# Debugger.net
KiCad netlist of a schematic drawn in Altium Designer
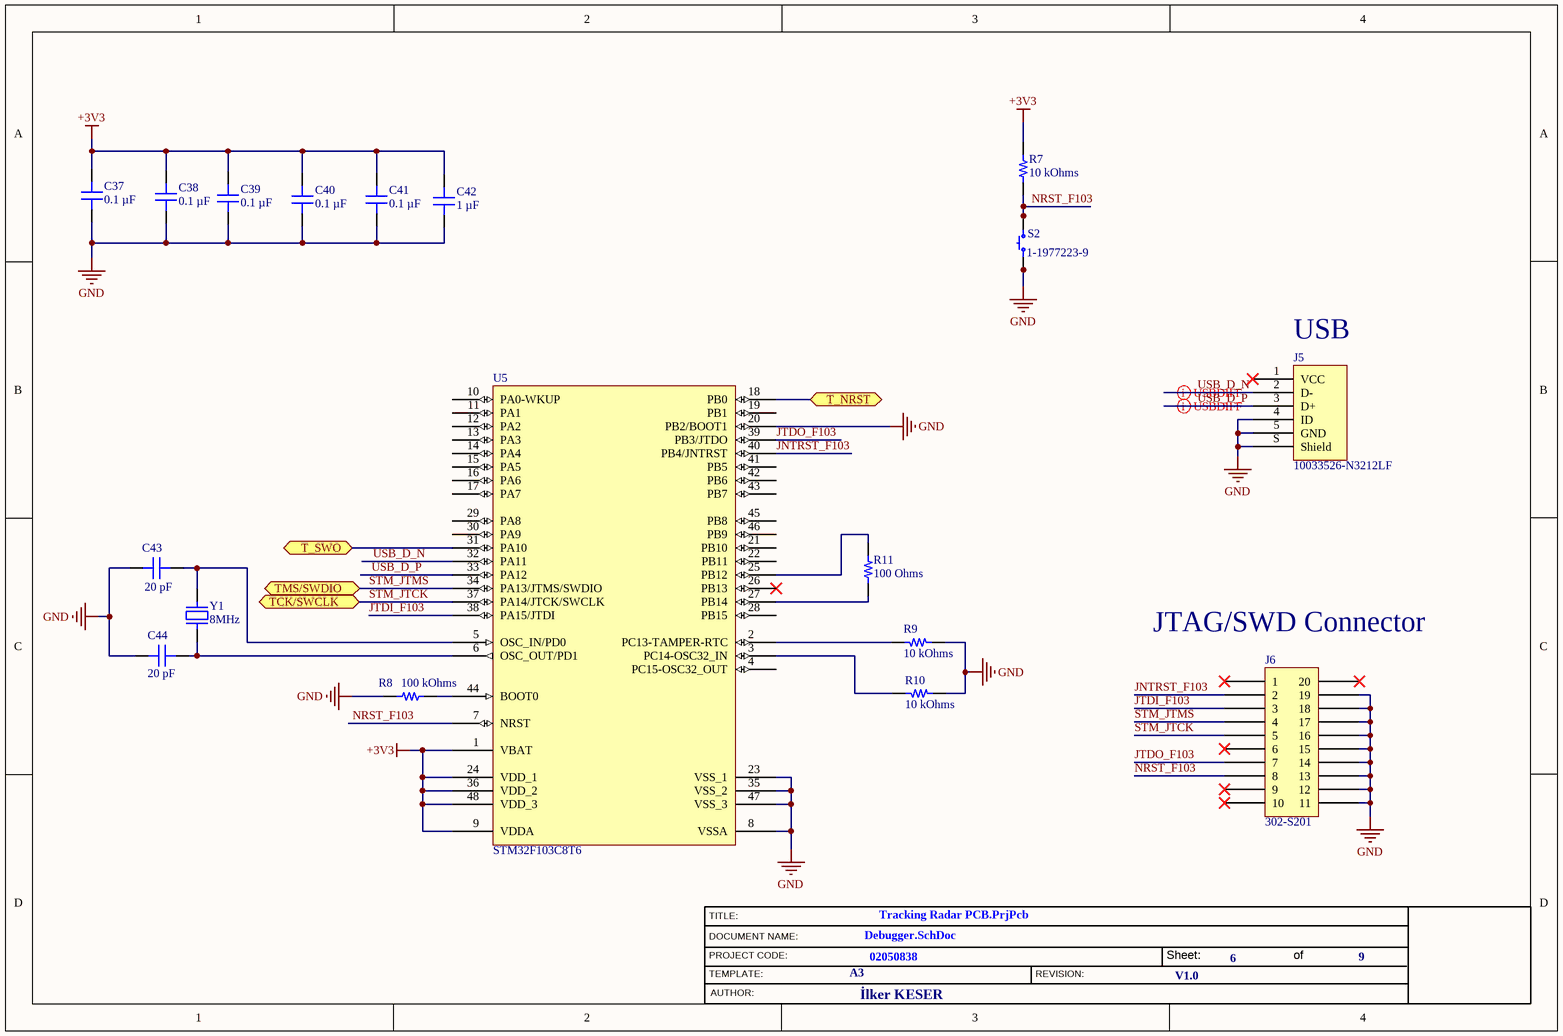
[diagram p0: Debugger.SchDoc]

(export (version "E")
  (design (tool "Eeschema 10.0.6"))
  (components
    (comp (ref "C37")
      (value "0.1 µF")
      (footprint "CAP 0402_1005")
      (description "CAP CER 0.1UF 6.3V X5R 0402")
      (fields
        (field (name "PART NUMBER") "C0402C104M9PAC7867")
        (field (name "CAPACITANCE") "0.1 µF")
        (field (name "MANUFACTURER") "KEMET")
      )
      (libsource (lib "Celestial Altium Library - altium_library") (part "Capacitor"))
    )
    (comp (ref "C38")
      (value "0.1 µF")
      (footprint "CAP 0402_1005")
      (description "CAP CER 0.1UF 6.3V X5R 0402")
      (fields
        (field (name "PART NUMBER") "C0402C104M9PAC7867")
        (field (name "CAPACITANCE") "0.1 µF")
        (field (name "MANUFACTURER") "KEMET")
      )
      (libsource (lib "Celestial Altium Library - altium_library") (part "Capacitor"))
    )
    (comp (ref "C39")
      (value "0.1 µF")
      (footprint "CAP 0402_1005")
      (description "CAP CER 0.1UF 6.3V X5R 0402")
      (fields
        (field (name "PART NUMBER") "C0402C104M9PAC7867")
        (field (name "CAPACITANCE") "0.1 µF")
        (field (name "MANUFACTURER") "KEMET")
      )
      (libsource (lib "Celestial Altium Library - altium_library") (part "Capacitor"))
    )
    (comp (ref "C40")
      (value "0.1 µF")
      (footprint "CAP 0402_1005")
      (description "CAP CER 0.1UF 6.3V X5R 0402")
      (fields
        (field (name "PART NUMBER") "C0402C104M9PAC7867")
        (field (name "CAPACITANCE") "0.1 µF")
        (field (name "MANUFACTURER") "KEMET")
      )
      (libsource (lib "Celestial Altium Library - altium_library") (part "Capacitor"))
    )
    (comp (ref "C41")
      (value "0.1 µF")
      (footprint "CAP 0402_1005")
      (description "CAP CER 0.1UF 6.3V X5R 0402")
      (fields
        (field (name "PART NUMBER") "C0402C104M9PAC7867")
        (field (name "CAPACITANCE") "0.1 µF")
        (field (name "MANUFACTURER") "KEMET")
      )
      (libsource (lib "Celestial Altium Library - altium_library") (part "Capacitor"))
    )
    (comp (ref "C42")
      (value "1 µF")
      (footprint "CAP 0402_1005")
      (description "CAP CER 1UF 6.3V X5R 0402")
      (fields
        (field (name "PART NUMBER") "GRM152R60J105ME15D")
        (field (name "CAPACITANCE") "1 µF")
        (field (name "MANUFACTURER") "Murata Electronics")
      )
      (libsource (lib "Celestial Altium Library - altium_library") (part "Capacitor"))
    )
    (comp (ref "C43")
      (value "20 pF")
      (footprint "CAP 0402_1005")
      (description "CAP CER 20PF 10V NP0 0402")
      (fields
        (field (name "PART NUMBER") "C0402C200K8GAC7867")
        (field (name "CAPACITANCE") "20 pF")
        (field (name "MANUFACTURER") "KEMET")
      )
      (libsource (lib "Celestial Altium Library - altium_library") (part "Capacitor"))
    )
    (comp (ref "C44")
      (value "20 pF")
      (footprint "CAP 0402_1005")
      (description "CAP CER 20PF 10V NP0 0402")
      (fields
        (field (name "PART NUMBER") "C0402C200K8GAC7867")
        (field (name "CAPACITANCE") "20 pF")
        (field (name "MANUFACTURER") "KEMET")
      )
      (libsource (lib "Celestial Altium Library - altium_library") (part "Capacitor"))
    )
    (comp (ref "J5")
      (value "10033526-N3212LF")
      (footprint "FCI USB 10033526-N3212LF")
      (description "CONN RCPT MINI USB B 5POS SMD RA")
      (fields (field (name "MANUFACTURER") "Amphenol ICC (FCI)"))
      (libsource (lib "Celestial Altium Library - altium_library") (part "USB 2.0 Type B Micro"))
    )
    (comp (ref "J6")
      (value "302-S201")
      (footprint "OST 302-S201")
      (description "CONN HEADER VERT 20POS 2.54MM")
      (fields (field (name "MANUFACTURER") "On Shore Technology Inc."))
      (libsource (lib "Celestial Altium Library - altium_library") (part "20 Pin Dual Row"))
    )
    (comp (ref "R7")
      (value "10 kOhms")
      (footprint "KOA RES RK73 RN73 0402_1005")
      (description "RES 10K OHM 0.5% 1/10W 0402")
      (fields
        (field (name "PART NUMBER") "RK73H1ETTP1002D")
        (field (name "MANUFACTURER") "KOA Speer Electronics, Inc.")
      )
      (libsource (lib "Celestial Altium Library - altium_library") (part "Resistor"))
    )
    (comp (ref "R8")
      (value "100 kOhms")
      (footprint "YAGEO RES 0402_1005")
      (description "RES 100K OHM 0.1% 1/16W 0402")
      (fields (field (name "PART NUMBER") "RP0402BRD07100KL") (field (name "MANUFACTURER") "Yageo"))
      (libsource (lib "Celestial Altium Library - altium_library") (part "Resistor"))
    )
    (comp (ref "R9")
      (value "10 kOhms")
      (footprint "KOA RES RK73 RN73 0402_1005")
      (description "RES 10K OHM 0.5% 1/10W 0402")
      (fields
        (field (name "PART NUMBER") "RK73H1ETTP1002D")
        (field (name "MANUFACTURER") "KOA Speer Electronics, Inc.")
      )
      (libsource (lib "Celestial Altium Library - altium_library") (part "Resistor"))
    )
    (comp (ref "R10")
      (value "10 kOhms")
      (footprint "KOA RES RK73 RN73 0402_1005")
      (description "RES 10K OHM 0.5% 1/10W 0402")
      (fields
        (field (name "PART NUMBER") "RK73H1ETTP1002D")
        (field (name "MANUFACTURER") "KOA Speer Electronics, Inc.")
      )
      (libsource (lib "Celestial Altium Library - altium_library") (part "Resistor"))
    )
    (comp (ref "R11")
      (value "100 Ohms")
      (footprint "YAGEO RES 0402_1005")
      (description "RES 100 OHM 0.1% 1/16W 0402")
      (fields (field (name "PART NUMBER") "RP0402BRD07100RL") (field (name "MANUFACTURER") "Yageo"))
      (libsource (lib "Celestial Altium Library - altium_library") (part "Resistor"))
    )
    (comp (ref "S2")
      (value "1-1977223-9")
      (footprint "TE FSM6JSMA")
      (description "SWITCH TACTILE SPST-NO 0.05A 24V")
      (fields (field (name "MANUFACTURER") "TE Connectivity ALCOSWITCH Switches"))
      (libsource (lib "Celestial Altium Library - altium_library") (part "SPST-NO 4 PIN"))
    )
    (comp (ref "U5")
      (value "STM32F103C8T6")
      (footprint "LQFP48_L")
      (description "STM32 ARM-based 32-bit MCU with 64 Kbytes Flash, 48-pin LQFP, Industrial Temperature")
      (fields (field (name "PUBLISHER") "Altium Limited"))
      (libsource (lib "ST Microcontroller 32-Bit STM32") (part "STM32F103C8T6"))
    )
    (comp (ref "Y1")
      (value "8MHz")
      (footprint "TXC 9C")
      (description "CRYSTAL 8.0000MHZ 20PF SMD")
      (fields (field (name "PART NUMBER") "9C-8.000MBBK-T") (field (name "MANUFACTURER") "TXC CORPORATION"))
      (libsource (lib "Celestial Altium Library - altium_library") (part "TXC Crystal 9C"))
    )
  )
  (nets
    (net (code "1") (name "+3V3") (class "Default")
      (node (ref "C37") (pin "2") (pinfunction "2_2") (pintype "passive"))
      (node (ref "C38") (pin "2") (pinfunction "2_2") (pintype "passive"))
      (node (ref "C39") (pin "2") (pinfunction "2_2") (pintype "passive"))
      (node (ref "C40") (pin "2") (pinfunction "2_2") (pintype "passive"))
      (node (ref "C41") (pin "2") (pinfunction "2_2") (pintype "passive"))
      (node (ref "C42") (pin "2") (pinfunction "2_2") (pintype "passive"))
      (node (ref "R7") (pin "1") (pinfunction "1_1") (pintype "passive"))
      (node (ref "U5") (pin "1") (pinfunction "VBAT_1") (pintype "power_in"))
      (node (ref "U5") (pin "24") (pinfunction "VDD_1_24") (pintype "power_in"))
      (node (ref "U5") (pin "36") (pinfunction "VDD_2_36") (pintype "power_in"))
      (node (ref "U5") (pin "48") (pinfunction "VDD_3_48") (pintype "power_in"))
      (node (ref "U5") (pin "9") (pinfunction "VDDA_9") (pintype "power_in"))
    )
    (net (code "2") (name "/JNTRST_F103") (class "Default")
      (node (ref "J6") (pin "2") (pinfunction "2_2") (pintype "passive"))
      (node (ref "U5") (pin "40") (pinfunction "PB4/JNTRST_40") (pintype "bidirectional"))
    )
    (net (code "3") (name "/JTDI_F103") (class "Default")
      (node (ref "J6") (pin "3") (pinfunction "3_3") (pintype "passive"))
      (node (ref "U5") (pin "38") (pinfunction "PA15/JTDI_38") (pintype "bidirectional"))
    )
    (net (code "4") (name "/JTDO_F103") (class "Default")
      (node (ref "J6") (pin "7") (pinfunction "7_7") (pintype "passive"))
      (node (ref "U5") (pin "39") (pinfunction "PB3/JTDO_39") (pintype "bidirectional"))
    )
    (net (code "5") (name "/NRST_F103") (class "Default")
      (node (ref "J6") (pin "8") (pinfunction "8_8") (pintype "passive"))
      (node (ref "R7") (pin "2") (pinfunction "2_2") (pintype "passive"))
      (node (ref "S2") (pin "3") (pinfunction "3_3") (pintype "passive"))
      (node (ref "S2") (pin "4") (pinfunction "4_4") (pintype "passive"))
      (node (ref "U5") (pin "7") (pinfunction "NRST_7") (pintype "bidirectional"))
    )
    (net (code "6") (name "/STM_JTCK") (class "Default")
      (node (ref "J6") (pin "5") (pinfunction "5_5") (pintype "passive"))
      (node (ref "U5") (pin "37") (pinfunction "PA14/JTCK/SWCLK_37") (pintype "bidirectional"))
    )
    (net (code "7") (name "/STM_JTMS") (class "Default")
      (node (ref "J6") (pin "4") (pinfunction "4_4") (pintype "passive"))
      (node (ref "U5") (pin "34") (pinfunction "PA13/JTMS/SWDIO_34") (pintype "bidirectional"))
    )
    (net (code "8") (name "/T_NRST") (class "Default")
      (node (ref "U5") (pin "18") (pinfunction "PB0_18") (pintype "bidirectional"))
    )
    (net (code "9") (name "/T_SWO") (class "Default")
      (node (ref "U5") (pin "31") (pinfunction "PA10_31") (pintype "bidirectional"))
    )
    (net (code "10") (name "/USB_D_N") (class "Default")
      (node (ref "J5") (pin "2") (pinfunction "D-_2") (pintype "passive"))
      (node (ref "U5") (pin "32") (pinfunction "PA11_32") (pintype "bidirectional"))
    )
    (net (code "11") (name "/USB_D_P") (class "Default")
      (node (ref "J5") (pin "3") (pinfunction "D+_3") (pintype "passive"))
      (node (ref "U5") (pin "33") (pinfunction "PA12_33") (pintype "bidirectional"))
    )
    (net (code "12") (name "GND") (class "Default")
      (node (ref "C37") (pin "1") (pinfunction "1_1") (pintype "passive"))
      (node (ref "C38") (pin "1") (pinfunction "1_1") (pintype "passive"))
      (node (ref "C39") (pin "1") (pinfunction "1_1") (pintype "passive"))
      (node (ref "C40") (pin "1") (pinfunction "1_1") (pintype "passive"))
      (node (ref "C41") (pin "1") (pinfunction "1_1") (pintype "passive"))
      (node (ref "C42") (pin "1") (pinfunction "1_1") (pintype "passive"))
      (node (ref "C43") (pin "1") (pinfunction "1_1") (pintype "passive"))
      (node (ref "C44") (pin "1") (pinfunction "1_1") (pintype "passive"))
      (node (ref "J5") (pin "4") (pinfunction "ID_4") (pintype "passive"))
      (node (ref "J5") (pin "5") (pinfunction "GND_5") (pintype "passive"))
      (node (ref "J5") (pin "S") (pinfunction "Shield_S") (pintype "passive"))
      (node (ref "J6") (pin "11") (pinfunction "11_11") (pintype "passive"))
      (node (ref "J6") (pin "12") (pinfunction "12_12") (pintype "passive"))
      (node (ref "J6") (pin "13") (pinfunction "13_13") (pintype "passive"))
      (node (ref "J6") (pin "14") (pinfunction "14_14") (pintype "passive"))
      (node (ref "J6") (pin "15") (pinfunction "15_15") (pintype "passive"))
      (node (ref "J6") (pin "16") (pinfunction "16_16") (pintype "passive"))
      (node (ref "J6") (pin "17") (pinfunction "17_17") (pintype "passive"))
      (node (ref "J6") (pin "18") (pinfunction "18_18") (pintype "passive"))
      (node (ref "J6") (pin "19") (pinfunction "19_19") (pintype "passive"))
      (node (ref "R10") (pin "2") (pinfunction "2_2") (pintype "passive"))
      (node (ref "R8") (pin "1") (pinfunction "1_1") (pintype "passive"))
      (node (ref "R9") (pin "2") (pinfunction "2_2") (pintype "passive"))
      (node (ref "S2") (pin "1") (pinfunction "1_1") (pintype "passive"))
      (node (ref "S2") (pin "2") (pinfunction "2_2") (pintype "passive"))
      (node (ref "U5") (pin "20") (pinfunction "PB2/BOOT1_20") (pintype "bidirectional"))
      (node (ref "U5") (pin "23") (pinfunction "VSS_1_23") (pintype "power_in"))
      (node (ref "U5") (pin "35") (pinfunction "VSS_2_35") (pintype "power_in"))
      (node (ref "U5") (pin "47") (pinfunction "VSS_3_47") (pintype "power_in"))
      (node (ref "U5") (pin "8") (pinfunction "VSSA_8") (pintype "power_in"))
    )
    (net (code "13") (name "Net-(U5-BOOT0)") (class "Default")
      (node (ref "R8") (pin "2") (pinfunction "2_2") (pintype "passive"))
      (node (ref "U5") (pin "44") (pinfunction "BOOT0_44") (pintype "input"))
    )
    (net (code "14") (name "Net-(U5-OSC_IN{slash}PD0)") (class "Default")
      (node (ref "C43") (pin "2") (pinfunction "2_2") (pintype "passive"))
      (node (ref "U5") (pin "5") (pinfunction "OSC_IN/PD0_5") (pintype "input"))
      (node (ref "Y1") (pin "2") (pinfunction "2_2") (pintype "passive"))
    )
    (net (code "15") (name "Net-(U5-OSC_OUT{slash}PD1)") (class "Default")
      (node (ref "C44") (pin "2") (pinfunction "2_2") (pintype "passive"))
      (node (ref "U5") (pin "6") (pinfunction "OSC_OUT/PD1_6") (pintype "output"))
      (node (ref "Y1") (pin "1") (pinfunction "1_1") (pintype "passive"))
    )
    (net (code "16") (name "Net-(U5-PB12)") (class "Default")
      (node (ref "R11") (pin "2") (pinfunction "2_2") (pintype "passive"))
      (node (ref "U5") (pin "25") (pinfunction "PB12_25") (pintype "bidirectional"))
    )
    (net (code "17") (name "Net-(U5-PB14)") (class "Default")
      (node (ref "R11") (pin "1") (pinfunction "1_1") (pintype "passive"))
      (node (ref "U5") (pin "27") (pinfunction "PB14_27") (pintype "bidirectional"))
    )
    (net (code "18") (name "Net-(U5-PC13-TAMPER-RTC)") (class "Default")
      (node (ref "R9") (pin "1") (pinfunction "1_1") (pintype "passive"))
      (node (ref "U5") (pin "2") (pinfunction "PC13-TAMPER-RTC_2") (pintype "bidirectional"))
    )
    (net (code "19") (name "Net-(U5-PC14-OSC32_IN)") (class "Default")
      (node (ref "R10") (pin "1") (pinfunction "1_1") (pintype "passive"))
      (node (ref "U5") (pin "3") (pinfunction "PC14-OSC32_IN_3") (pintype "bidirectional"))
    )
    (net (code "20") (name "unconnected-(J5-VCC-Pad1)") (class "Default")
      (node (ref "J5") (pin "1") (pinfunction "VCC_1") (pintype "passive+no_connect"))
    )
    (net (code "21") (name "unconnected-(J6-Pad1)") (class "Default")
      (node (ref "J6") (pin "1") (pinfunction "1_1") (pintype "passive+no_connect"))
    )
    (net (code "22") (name "unconnected-(J6-Pad6)") (class "Default")
      (node (ref "J6") (pin "6") (pinfunction "6_6") (pintype "passive+no_connect"))
    )
    (net (code "23") (name "unconnected-(J6-Pad9)") (class "Default")
      (node (ref "J6") (pin "9") (pinfunction "9_9") (pintype "passive+no_connect"))
    )
    (net (code "24") (name "unconnected-(J6-Pad10)") (class "Default")
      (node (ref "J6") (pin "10") (pinfunction "10_10") (pintype "passive+no_connect"))
    )
    (net (code "25") (name "unconnected-(J6-Pad20)") (class "Default")
      (node (ref "J6") (pin "20") (pinfunction "20_20") (pintype "passive+no_connect"))
    )
    (net (code "26") (name "unconnected-(U5-PA0-WKUP-Pad10)") (class "Default")
      (node (ref "U5") (pin "10") (pinfunction "PA0-WKUP_10") (pintype "bidirectional"))
    )
    (net (code "27") (name "unconnected-(U5-PA1-Pad11)") (class "Default")
      (node (ref "U5") (pin "11") (pinfunction "PA1_11") (pintype "bidirectional"))
    )
    (net (code "28") (name "unconnected-(U5-PA2-Pad12)") (class "Default")
      (node (ref "U5") (pin "12") (pinfunction "PA2_12") (pintype "bidirectional"))
    )
    (net (code "29") (name "unconnected-(U5-PA3-Pad13)") (class "Default")
      (node (ref "U5") (pin "13") (pinfunction "PA3_13") (pintype "bidirectional"))
    )
    (net (code "30") (name "unconnected-(U5-PA4-Pad14)") (class "Default")
      (node (ref "U5") (pin "14") (pinfunction "PA4_14") (pintype "bidirectional"))
    )
    (net (code "31") (name "unconnected-(U5-PA5-Pad15)") (class "Default")
      (node (ref "U5") (pin "15") (pinfunction "PA5_15") (pintype "bidirectional"))
    )
    (net (code "32") (name "unconnected-(U5-PA6-Pad16)") (class "Default")
      (node (ref "U5") (pin "16") (pinfunction "PA6_16") (pintype "bidirectional"))
    )
    (net (code "33") (name "unconnected-(U5-PA7-Pad17)") (class "Default")
      (node (ref "U5") (pin "17") (pinfunction "PA7_17") (pintype "bidirectional"))
    )
    (net (code "34") (name "unconnected-(U5-PA8-Pad29)") (class "Default")
      (node (ref "U5") (pin "29") (pinfunction "PA8_29") (pintype "bidirectional"))
    )
    (net (code "35") (name "unconnected-(U5-PA9-Pad30)") (class "Default")
      (node (ref "U5") (pin "30") (pinfunction "PA9_30") (pintype "bidirectional"))
    )
    (net (code "36") (name "unconnected-(U5-PB1-Pad19)") (class "Default")
      (node (ref "U5") (pin "19") (pinfunction "PB1_19") (pintype "bidirectional"))
    )
    (net (code "37") (name "unconnected-(U5-PB5-Pad41)") (class "Default")
      (node (ref "U5") (pin "41") (pinfunction "PB5_41") (pintype "bidirectional"))
    )
    (net (code "38") (name "unconnected-(U5-PB6-Pad42)") (class "Default")
      (node (ref "U5") (pin "42") (pinfunction "PB6_42") (pintype "bidirectional"))
    )
    (net (code "39") (name "unconnected-(U5-PB7-Pad43)") (class "Default")
      (node (ref "U5") (pin "43") (pinfunction "PB7_43") (pintype "bidirectional"))
    )
    (net (code "40") (name "unconnected-(U5-PB8-Pad45)") (class "Default")
      (node (ref "U5") (pin "45") (pinfunction "PB8_45") (pintype "bidirectional"))
    )
    (net (code "41") (name "unconnected-(U5-PB9-Pad46)") (class "Default")
      (node (ref "U5") (pin "46") (pinfunction "PB9_46") (pintype "bidirectional"))
    )
    (net (code "42") (name "unconnected-(U5-PB10-Pad21)") (class "Default")
      (node (ref "U5") (pin "21") (pinfunction "PB10_21") (pintype "bidirectional"))
    )
    (net (code "43") (name "unconnected-(U5-PB11-Pad22)") (class "Default")
      (node (ref "U5") (pin "22") (pinfunction "PB11_22") (pintype "bidirectional"))
    )
    (net (code "44") (name "unconnected-(U5-PB13-Pad26)") (class "Default")
      (node (ref "U5") (pin "26") (pinfunction "PB13_26") (pintype "bidirectional+no_connect"))
    )
    (net (code "45") (name "unconnected-(U5-PB15-Pad28)") (class "Default")
      (node (ref "U5") (pin "28") (pinfunction "PB15_28") (pintype "bidirectional"))
    )
    (net (code "46") (name "unconnected-(U5-PC15-OSC32_OUT-Pad4)") (class "Default")
      (node (ref "U5") (pin "4") (pinfunction "PC15-OSC32_OUT_4") (pintype "bidirectional"))
    )
  )
)
